# RFMultiOut.net
KiCad netlist of a schematic drawn in EAGLE
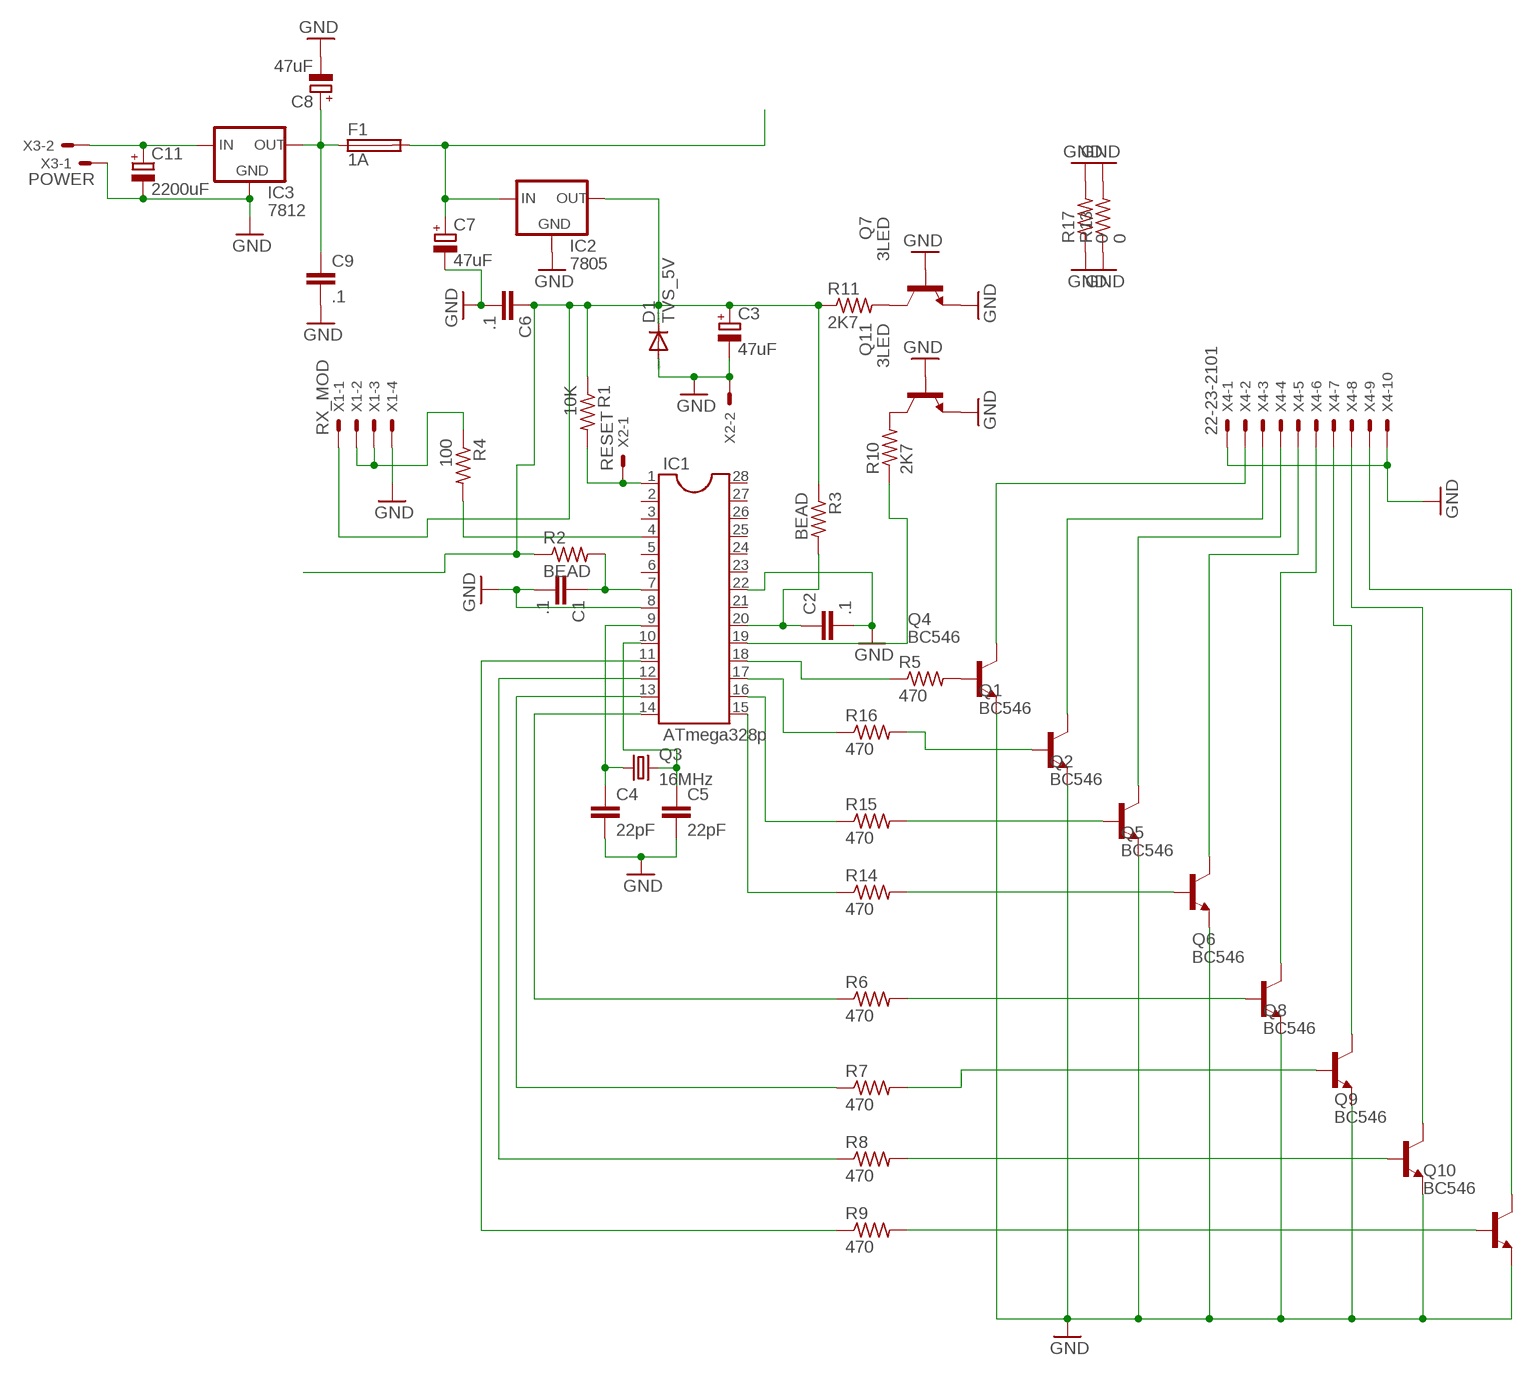
[diagram p0: schematic, sheet 1]

(export (version "E")
  (design (tool "Eeschema 10.0.6"))
  (components
    (comp (ref "C1")
      (value ".1")
      (footprint "eagle-import:C1210K")
      (libsource (lib "eagle-import") (part "C-EUC1210K"))
    )
    (comp (ref "C2")
      (value ".1")
      (footprint "eagle-import:C1210K")
      (libsource (lib "eagle-import") (part "C-EUC1210K"))
    )
    (comp (ref "C3")
      (value "47uF")
      (footprint "eagle-import:E5-8,5")
      (libsource (lib "eagle-import") (part "CPOL-EUE5-8.5"))
    )
    (comp (ref "C4")
      (value "22pF")
      (footprint "eagle-import:C1210K")
      (libsource (lib "eagle-import") (part "C-EUC1210K"))
    )
    (comp (ref "C5")
      (value "22pF")
      (footprint "eagle-import:C1210K")
      (libsource (lib "eagle-import") (part "C-EUC1210K"))
    )
    (comp (ref "C6")
      (value ".1")
      (footprint "eagle-import:C1210K")
      (libsource (lib "eagle-import") (part "C-EUC1210K"))
    )
    (comp (ref "C7")
      (value "47uF")
      (footprint "eagle-import:E5-8,5")
      (libsource (lib "eagle-import") (part "CPOL-EUE5-8.5"))
    )
    (comp (ref "C8")
      (value "47uF")
      (footprint "eagle-import:E5-8,5")
      (libsource (lib "eagle-import") (part "CPOL-EUE5-8.5"))
    )
    (comp (ref "C9")
      (value ".1")
      (footprint "eagle-import:C1210K")
      (libsource (lib "eagle-import") (part "C-EUC1210K"))
    )
    (comp (ref "C11")
      (value "2200uF")
      (footprint "eagle-import:E5-8,5")
      (libsource (lib "eagle-import") (part "CPOL-EUE5-8.5"))
    )
    (comp (ref "D1")
      (value "TVS_5V")
      (footprint "eagle-import:DO35-10")
      (libsource (lib "eagle-import") (part "1N4148DO35-10"))
    )
    (comp (ref "F1")
      (value "1A")
      (footprint "eagle-import:19560")
      (fields (field (name "MPN") "56000001009"))
      (libsource (lib "eagle-import") (part "19560"))
    )
    (comp (ref "IC1")
      (value "ATmega328p")
      (footprint "eagle-import:DIL28-3")
      (libsource (lib "eagle-import") (part "DIL28-3"))
    )
    (comp (ref "IC2")
      (value "7805")
      (footprint "eagle-import:78XXS")
      (libsource (lib "eagle-import") (part "78XXS"))
    )
    (comp (ref "IC3")
      (value "7812")
      (footprint "eagle-import:78XXS")
      (libsource (lib "eagle-import") (part "78XXS"))
    )
    (comp (ref "Q1")
      (value "BC546")
      (footprint "eagle-import:TO92-EBC")
      (libsource (lib "eagle-import") (part "BC546B"))
    )
    (comp (ref "Q2")
      (value "BC546")
      (footprint "eagle-import:TO92-EBC")
      (libsource (lib "eagle-import") (part "BC546B"))
    )
    (comp (ref "Q3")
      (value "16MHz")
      (footprint "eagle-import:HC49_S")
      (libsource (lib "eagle-import") (part "CRYSTALHC49S"))
    )
    (comp (ref "Q4")
      (value "BC546")
      (footprint "eagle-import:TO92-EBC")
      (libsource (lib "eagle-import") (part "BC546B"))
    )
    (comp (ref "Q5")
      (value "BC546")
      (footprint "eagle-import:TO92-EBC")
      (libsource (lib "eagle-import") (part "BC546B"))
    )
    (comp (ref "Q6")
      (value "BC546")
      (footprint "eagle-import:TO92-EBC")
      (libsource (lib "eagle-import") (part "BC546B"))
    )
    (comp (ref "Q7")
      (value "3LED")
      (footprint "eagle-import:TO92-EBC")
      (libsource (lib "eagle-import") (part "BC546A"))
    )
    (comp (ref "Q8")
      (value "BC546")
      (footprint "eagle-import:TO92-EBC")
      (libsource (lib "eagle-import") (part "BC546B"))
    )
    (comp (ref "Q9")
      (value "BC546")
      (footprint "eagle-import:TO92-EBC")
      (libsource (lib "eagle-import") (part "BC546B"))
    )
    (comp (ref "Q10")
      (value "BC546")
      (footprint "eagle-import:TO92-EBC")
      (libsource (lib "eagle-import") (part "BC546B"))
    )
    (comp (ref "Q11")
      (value "3LED")
      (footprint "eagle-import:TO92-EBC")
      (libsource (lib "eagle-import") (part "BC546A"))
    )
    (comp (ref "R1")
      (value "10K")
      (footprint "eagle-import:0309_10")
      (libsource (lib "eagle-import") (part "R-US_0309/10"))
    )
    (comp (ref "R2")
      (value "BEAD")
      (footprint "eagle-import:0309_10")
      (libsource (lib "eagle-import") (part "R-US_0309/10"))
    )
    (comp (ref "R3")
      (value "BEAD")
      (footprint "eagle-import:0309_12")
      (libsource (lib "eagle-import") (part "R-US_0309/12"))
    )
    (comp (ref "R4")
      (value "100")
      (footprint "eagle-import:0207_15")
      (libsource (lib "eagle-import") (part "R-US_0207/15"))
    )
    (comp (ref "R5")
      (value "470")
      (footprint "eagle-import:R1210")
      (libsource (lib "eagle-import") (part "R-US_R1210"))
    )
    (comp (ref "R6")
      (value "470")
      (footprint "eagle-import:R1210")
      (libsource (lib "eagle-import") (part "R-US_R1210"))
    )
    (comp (ref "R7")
      (value "470")
      (footprint "eagle-import:R1210")
      (libsource (lib "eagle-import") (part "R-US_R1210"))
    )
    (comp (ref "R8")
      (value "470")
      (footprint "eagle-import:R1210")
      (libsource (lib "eagle-import") (part "R-US_R1210"))
    )
    (comp (ref "R9")
      (value "470")
      (footprint "eagle-import:R1210")
      (libsource (lib "eagle-import") (part "R-US_R1210"))
    )
    (comp (ref "R10")
      (value "2K7")
      (footprint "eagle-import:0309_10")
      (libsource (lib "eagle-import") (part "R-US_0309/10"))
    )
    (comp (ref "R11")
      (value "2K7")
      (footprint "eagle-import:0309_10")
      (libsource (lib "eagle-import") (part "R-US_0309/10"))
    )
    (comp (ref "R13")
      (value "0")
      (footprint "eagle-import:0309_10")
      (libsource (lib "eagle-import") (part "R-US_0309/10"))
    )
    (comp (ref "R14")
      (value "470")
      (footprint "eagle-import:R1210")
      (libsource (lib "eagle-import") (part "R-US_R1210"))
    )
    (comp (ref "R15")
      (value "470")
      (footprint "eagle-import:R1210")
      (libsource (lib "eagle-import") (part "R-US_R1210"))
    )
    (comp (ref "R16")
      (value "470")
      (footprint "eagle-import:R1210")
      (libsource (lib "eagle-import") (part "R-US_R1210"))
    )
    (comp (ref "R17")
      (value "0")
      (footprint "eagle-import:0309_10")
      (libsource (lib "eagle-import") (part "R-US_0309/10"))
    )
    (comp (ref "X1")
      (value "RX_MOD")
      (footprint "eagle-import:22-23-2041")
      (fields (field (name "MF") "MOLEX") (field (name "MPN") "22-23-2041"))
      (libsource (lib "eagle-import") (part "22-23-2041"))
    )
    (comp (ref "X2")
      (value "RESET")
      (footprint "eagle-import:22-23-2021")
      (fields (field (name "MF") "MOLEX") (field (name "MPN") "22-23-2021"))
      (libsource (lib "eagle-import") (part "22-23-2021"))
    )
    (comp (ref "X3")
      (value "POWER")
      (footprint "eagle-import:22-23-2021")
      (fields (field (name "MF") "MOLEX") (field (name "MPN") "22-23-2021"))
      (libsource (lib "eagle-import") (part "22-23-2021"))
    )
    (comp (ref "X4")
      (value "22-23-2101")
      (footprint "eagle-import:22-23-2101")
      (fields (field (name "MF") "MOLEX"))
      (libsource (lib "eagle-import") (part "22-23-2101"))
    )
  )
  (nets
    (net (code "1") (name "GND") (class "Default")
      (node (ref "C1") (pin "2") (pinfunction "2_2") (pintype "passive"))
      (node (ref "C11") (pin "-") (pinfunction "-_-") (pintype "passive"))
      (node (ref "C2") (pin "2") (pinfunction "2_2") (pintype "passive"))
      (node (ref "C3") (pin "-") (pinfunction "-_-") (pintype "passive"))
      (node (ref "C4") (pin "2") (pinfunction "2_2") (pintype "passive"))
      (node (ref "C5") (pin "2") (pinfunction "2_2") (pintype "passive"))
      (node (ref "C6") (pin "2") (pinfunction "2_2") (pintype "passive"))
      (node (ref "C7") (pin "-") (pinfunction "-_-") (pintype "passive"))
      (node (ref "C8") (pin "-") (pinfunction "-_-") (pintype "passive"))
      (node (ref "C9") (pin "2") (pinfunction "2_2") (pintype "passive"))
      (node (ref "D1") (pin "A") (pinfunction "A_A") (pintype "passive"))
      (node (ref "IC1") (pin "22") (pinfunction "22_22") (pintype "passive"))
      (node (ref "IC1") (pin "8") (pinfunction "8_8") (pintype "passive"))
      (node (ref "IC2") (pin "GND") (pinfunction "GND_GND") (pintype "input"))
      (node (ref "IC3") (pin "GND") (pinfunction "GND_GND") (pintype "input"))
      (node (ref "Q1") (pin "E") (pinfunction "E_E") (pintype "passive"))
      (node (ref "Q10") (pin "E") (pinfunction "E_E") (pintype "passive"))
      (node (ref "Q11") (pin "B") (pinfunction "B_B") (pintype "passive"))
      (node (ref "Q11") (pin "E") (pinfunction "E_E") (pintype "passive"))
      (node (ref "Q2") (pin "E") (pinfunction "E_E") (pintype "passive"))
      (node (ref "Q4") (pin "E") (pinfunction "E_E") (pintype "passive"))
      (node (ref "Q5") (pin "E") (pinfunction "E_E") (pintype "passive"))
      (node (ref "Q6") (pin "E") (pinfunction "E_E") (pintype "passive"))
      (node (ref "Q7") (pin "B") (pinfunction "B_B") (pintype "passive"))
      (node (ref "Q7") (pin "E") (pinfunction "E_E") (pintype "passive"))
      (node (ref "Q8") (pin "E") (pinfunction "E_E") (pintype "passive"))
      (node (ref "Q9") (pin "E") (pinfunction "E_E") (pintype "passive"))
      (node (ref "R13") (pin "1") (pinfunction "1_1") (pintype "passive"))
      (node (ref "R13") (pin "2") (pinfunction "2_2") (pintype "passive"))
      (node (ref "R17") (pin "1") (pinfunction "1_1") (pintype "passive"))
      (node (ref "R17") (pin "2") (pinfunction "2_2") (pintype "passive"))
      (node (ref "X1") (pin "4") (pinfunction "S_4") (pintype "passive"))
      (node (ref "X2") (pin "2") (pinfunction "S_2") (pintype "passive"))
      (node (ref "X3") (pin "1") (pinfunction "S_1") (pintype "passive"))
      (node (ref "X4") (pin "1") (pinfunction "S_1") (pintype "passive"))
      (node (ref "X4") (pin "10") (pinfunction "S_10") (pintype "passive"))
    )
    (net (code "2") (name "Net-(C1-Pad1)") (class "Default")
      (node (ref "C1") (pin "1") (pinfunction "1_1") (pintype "passive"))
      (node (ref "IC1") (pin "7") (pinfunction "7_7") (pintype "passive"))
      (node (ref "R2") (pin "2") (pinfunction "2_2") (pintype "passive"))
    )
    (net (code "3") (name "Net-(C2-Pad1)") (class "Default")
      (node (ref "C2") (pin "1") (pinfunction "1_1") (pintype "passive"))
      (node (ref "IC1") (pin "20") (pinfunction "20_20") (pintype "passive"))
      (node (ref "R3") (pin "2") (pinfunction "2_2") (pintype "passive"))
    )
    (net (code "4") (name "Net-(C4-Pad1)") (class "Default")
      (node (ref "C4") (pin "1") (pinfunction "1_1") (pintype "passive"))
      (node (ref "IC1") (pin "9") (pinfunction "9_9") (pintype "passive"))
      (node (ref "Q3") (pin "1") (pinfunction "1_1") (pintype "passive"))
    )
    (net (code "5") (name "Net-(C5-Pad1)") (class "Default")
      (node (ref "C5") (pin "1") (pinfunction "1_1") (pintype "passive"))
      (node (ref "IC1") (pin "10") (pinfunction "10_10") (pintype "passive"))
      (node (ref "Q3") (pin "2") (pinfunction "2_2") (pintype "passive"))
    )
    (net (code "6") (name "Net-(C7-Pad+)") (class "Default")
      (node (ref "C7") (pin "+") (pinfunction "+_+") (pintype "passive"))
      (node (ref "F1") (pin "2") (pinfunction "2_2") (pintype "passive"))
      (node (ref "IC2") (pin "IN") (pinfunction "IN_IN") (pintype "input"))
    )
    (net (code "7") (name "Net-(C8-Pad+)") (class "Default")
      (node (ref "C8") (pin "+") (pinfunction "+_+") (pintype "passive"))
      (node (ref "C9") (pin "1") (pinfunction "1_1") (pintype "passive"))
      (node (ref "F1") (pin "1") (pinfunction "1_1") (pintype "passive"))
      (node (ref "IC3") (pin "OUT") (pinfunction "OUT_OUT") (pintype "passive"))
    )
    (net (code "8") (name "Net-(IC1-Pad4)") (class "Default")
      (node (ref "IC1") (pin "4") (pinfunction "4_4") (pintype "passive"))
      (node (ref "R4") (pin "2") (pinfunction "2_2") (pintype "passive"))
    )
    (net (code "9") (name "Net-(IC1-Pad11)") (class "Default")
      (node (ref "IC1") (pin "11") (pinfunction "11_11") (pintype "passive"))
      (node (ref "R9") (pin "1") (pinfunction "1_1") (pintype "passive"))
    )
    (net (code "10") (name "Net-(IC1-Pad12)") (class "Default")
      (node (ref "IC1") (pin "12") (pinfunction "12_12") (pintype "passive"))
      (node (ref "R8") (pin "1") (pinfunction "1_1") (pintype "passive"))
    )
    (net (code "11") (name "Net-(IC1-Pad13)") (class "Default")
      (node (ref "IC1") (pin "13") (pinfunction "13_13") (pintype "passive"))
      (node (ref "R7") (pin "1") (pinfunction "1_1") (pintype "passive"))
    )
    (net (code "12") (name "Net-(IC1-Pad14)") (class "Default")
      (node (ref "IC1") (pin "14") (pinfunction "14_14") (pintype "passive"))
      (node (ref "R6") (pin "1") (pinfunction "1_1") (pintype "passive"))
    )
    (net (code "13") (name "Net-(IC1-Pad15)") (class "Default")
      (node (ref "IC1") (pin "15") (pinfunction "15_15") (pintype "passive"))
      (node (ref "R14") (pin "1") (pinfunction "1_1") (pintype "passive"))
    )
    (net (code "14") (name "Net-(IC1-Pad16)") (class "Default")
      (node (ref "IC1") (pin "16") (pinfunction "16_16") (pintype "passive"))
      (node (ref "R15") (pin "1") (pinfunction "1_1") (pintype "passive"))
    )
    (net (code "15") (name "Net-(IC1-Pad17)") (class "Default")
      (node (ref "IC1") (pin "17") (pinfunction "17_17") (pintype "passive"))
      (node (ref "R16") (pin "1") (pinfunction "1_1") (pintype "passive"))
    )
    (net (code "16") (name "Net-(IC1-Pad18)") (class "Default")
      (node (ref "IC1") (pin "18") (pinfunction "18_18") (pintype "passive"))
      (node (ref "R5") (pin "1") (pinfunction "1_1") (pintype "passive"))
    )
    (net (code "17") (name "Net-(IC1-Pad19)") (class "Default")
      (node (ref "IC1") (pin "19") (pinfunction "19_19") (pintype "passive"))
      (node (ref "R10") (pin "1") (pinfunction "1_1") (pintype "passive"))
    )
    (net (code "18") (name "Net-(Q1-PadB)") (class "Default")
      (node (ref "Q1") (pin "B") (pinfunction "B_B") (pintype "passive"))
      (node (ref "R16") (pin "2") (pinfunction "2_2") (pintype "passive"))
    )
    (net (code "19") (name "Net-(Q2-PadB)") (class "Default")
      (node (ref "Q2") (pin "B") (pinfunction "B_B") (pintype "passive"))
      (node (ref "R15") (pin "2") (pinfunction "2_2") (pintype "passive"))
    )
    (net (code "20") (name "Net-(Q4-PadB)") (class "Default")
      (node (ref "Q4") (pin "B") (pinfunction "B_B") (pintype "passive"))
      (node (ref "R5") (pin "2") (pinfunction "2_2") (pintype "passive"))
    )
    (net (code "21") (name "Net-(Q5-PadB)") (class "Default")
      (node (ref "Q5") (pin "B") (pinfunction "B_B") (pintype "passive"))
      (node (ref "R14") (pin "2") (pinfunction "2_2") (pintype "passive"))
    )
    (net (code "22") (name "Net-(Q6-PadB)") (class "Default")
      (node (ref "Q6") (pin "B") (pinfunction "B_B") (pintype "passive"))
      (node (ref "R6") (pin "2") (pinfunction "2_2") (pintype "passive"))
    )
    (net (code "23") (name "Net-(Q7-PadC)") (class "Default")
      (node (ref "Q7") (pin "C") (pinfunction "C_C") (pintype "passive"))
      (node (ref "R11") (pin "2") (pinfunction "2_2") (pintype "passive"))
    )
    (net (code "24") (name "Net-(Q8-PadB)") (class "Default")
      (node (ref "Q8") (pin "B") (pinfunction "B_B") (pintype "passive"))
      (node (ref "R7") (pin "2") (pinfunction "2_2") (pintype "passive"))
    )
    (net (code "25") (name "Net-(Q9-PadB)") (class "Default")
      (node (ref "Q9") (pin "B") (pinfunction "B_B") (pintype "passive"))
      (node (ref "R8") (pin "2") (pinfunction "2_2") (pintype "passive"))
    )
    (net (code "26") (name "Net-(Q10-PadB)") (class "Default")
      (node (ref "Q10") (pin "B") (pinfunction "B_B") (pintype "passive"))
      (node (ref "R9") (pin "2") (pinfunction "2_2") (pintype "passive"))
    )
    (net (code "27") (name "Net-(Q11-PadC)") (class "Default")
      (node (ref "Q11") (pin "C") (pinfunction "C_C") (pintype "passive"))
      (node (ref "R10") (pin "2") (pinfunction "2_2") (pintype "passive"))
    )
    (net (code "28") (name "Net-(X1A-S)") (class "Default")
      (node (ref "C3") (pin "+") (pinfunction "+_+") (pintype "passive"))
      (node (ref "C6") (pin "1") (pinfunction "1_1") (pintype "passive"))
      (node (ref "D1") (pin "C") (pinfunction "C_C") (pintype "passive"))
      (node (ref "IC2") (pin "OUT") (pinfunction "OUT_OUT") (pintype "passive"))
      (node (ref "R1") (pin "1") (pinfunction "1_1") (pintype "passive"))
      (node (ref "R11") (pin "1") (pinfunction "1_1") (pintype "passive"))
      (node (ref "R2") (pin "1") (pinfunction "1_1") (pintype "passive"))
      (node (ref "R3") (pin "1") (pinfunction "1_1") (pintype "passive"))
      (node (ref "X1") (pin "1") (pinfunction "S_1") (pintype "passive"))
    )
    (net (code "29") (name "Net-(X1B-S)") (class "Default")
      (node (ref "R4") (pin "1") (pinfunction "1_1") (pintype "passive"))
      (node (ref "X1") (pin "2") (pinfunction "S_2") (pintype "passive"))
      (node (ref "X1") (pin "3") (pinfunction "S_3") (pintype "passive"))
    )
    (net (code "30") (name "Net-(X2A-S)") (class "Default")
      (node (ref "IC1") (pin "1") (pinfunction "1_1") (pintype "passive"))
      (node (ref "R1") (pin "2") (pinfunction "2_2") (pintype "passive"))
      (node (ref "X2") (pin "1") (pinfunction "S_1") (pintype "passive"))
    )
    (net (code "31") (name "Net-(X3B-S)") (class "Default")
      (node (ref "C11") (pin "+") (pinfunction "+_+") (pintype "passive"))
      (node (ref "IC3") (pin "IN") (pinfunction "IN_IN") (pintype "input"))
      (node (ref "X3") (pin "2") (pinfunction "S_2") (pintype "passive"))
    )
    (net (code "32") (name "Net-(X4C-S)") (class "Default")
      (node (ref "Q4") (pin "C") (pinfunction "C_C") (pintype "passive"))
      (node (ref "X4") (pin "2") (pinfunction "S_2") (pintype "passive"))
    )
    (net (code "33") (name "Net-(X4D-S)") (class "Default")
      (node (ref "Q1") (pin "C") (pinfunction "C_C") (pintype "passive"))
      (node (ref "X4") (pin "3") (pinfunction "S_3") (pintype "passive"))
    )
    (net (code "34") (name "Net-(X4E-S)") (class "Default")
      (node (ref "Q2") (pin "C") (pinfunction "C_C") (pintype "passive"))
      (node (ref "X4") (pin "4") (pinfunction "S_4") (pintype "passive"))
    )
    (net (code "35") (name "Net-(X4F-S)") (class "Default")
      (node (ref "Q5") (pin "C") (pinfunction "C_C") (pintype "passive"))
      (node (ref "X4") (pin "5") (pinfunction "S_5") (pintype "passive"))
    )
    (net (code "36") (name "Net-(X4G-S)") (class "Default")
      (node (ref "Q6") (pin "C") (pinfunction "C_C") (pintype "passive"))
      (node (ref "X4") (pin "6") (pinfunction "S_6") (pintype "passive"))
    )
    (net (code "37") (name "Net-(X4H-S)") (class "Default")
      (node (ref "Q8") (pin "C") (pinfunction "C_C") (pintype "passive"))
      (node (ref "X4") (pin "7") (pinfunction "S_7") (pintype "passive"))
    )
    (net (code "38") (name "Net-(X4I-S)") (class "Default")
      (node (ref "Q9") (pin "C") (pinfunction "C_C") (pintype "passive"))
      (node (ref "X4") (pin "8") (pinfunction "S_8") (pintype "passive"))
    )
    (net (code "39") (name "Net-(X4J-S)") (class "Default")
      (node (ref "Q10") (pin "C") (pinfunction "C_C") (pintype "passive"))
      (node (ref "X4") (pin "9") (pinfunction "S_9") (pintype "passive"))
    )
    (net (code "40") (name "unconnected-(IC1-Pad2)") (class "Default")
      (node (ref "IC1") (pin "2") (pinfunction "2_2") (pintype "passive"))
    )
    (net (code "41") (name "unconnected-(IC1-Pad3)") (class "Default")
      (node (ref "IC1") (pin "3") (pinfunction "3_3") (pintype "passive"))
    )
    (net (code "42") (name "unconnected-(IC1-Pad5)") (class "Default")
      (node (ref "IC1") (pin "5") (pinfunction "5_5") (pintype "passive"))
    )
    (net (code "43") (name "unconnected-(IC1-Pad6)") (class "Default")
      (node (ref "IC1") (pin "6") (pinfunction "6_6") (pintype "passive"))
    )
    (net (code "44") (name "unconnected-(IC1-Pad21)") (class "Default")
      (node (ref "IC1") (pin "21") (pinfunction "21_21") (pintype "passive"))
    )
    (net (code "45") (name "unconnected-(IC1-Pad23)") (class "Default")
      (node (ref "IC1") (pin "23") (pinfunction "23_23") (pintype "passive"))
    )
    (net (code "46") (name "unconnected-(IC1-Pad24)") (class "Default")
      (node (ref "IC1") (pin "24") (pinfunction "24_24") (pintype "passive"))
    )
    (net (code "47") (name "unconnected-(IC1-Pad25)") (class "Default")
      (node (ref "IC1") (pin "25") (pinfunction "25_25") (pintype "passive"))
    )
    (net (code "48") (name "unconnected-(IC1-Pad26)") (class "Default")
      (node (ref "IC1") (pin "26") (pinfunction "26_26") (pintype "passive"))
    )
    (net (code "49") (name "unconnected-(IC1-Pad27)") (class "Default")
      (node (ref "IC1") (pin "27") (pinfunction "27_27") (pintype "passive"))
    )
    (net (code "50") (name "unconnected-(IC1-Pad28)") (class "Default")
      (node (ref "IC1") (pin "28") (pinfunction "28_28") (pintype "passive"))
    )
  )
)
